# incubadora-v1.net
KiCad netlist of a schematic drawn in EAGLE
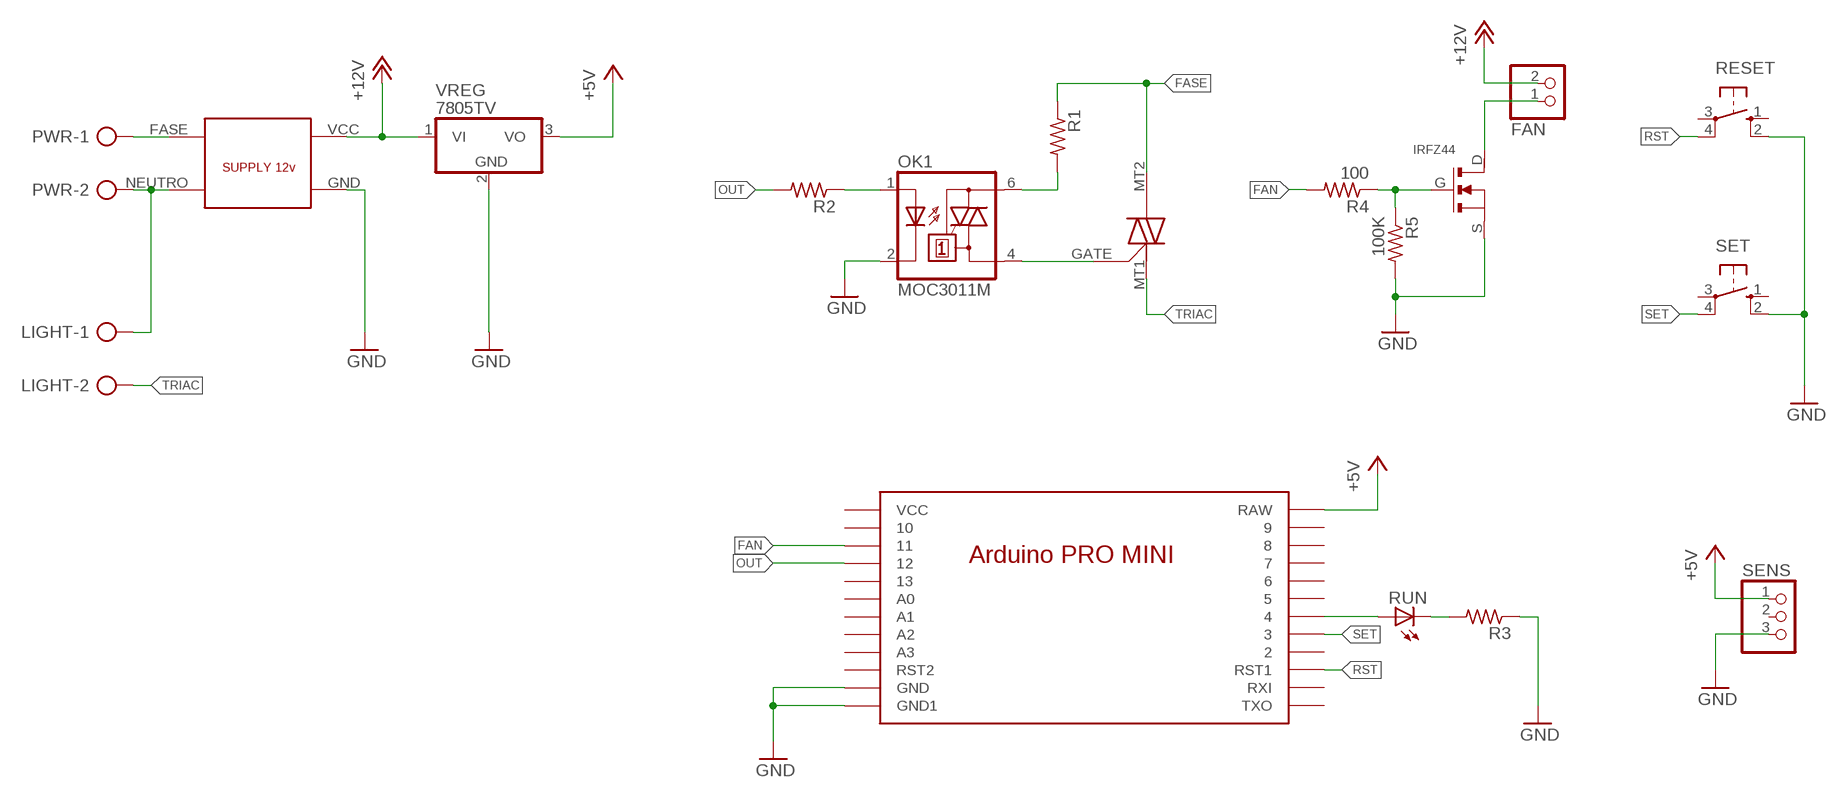
[diagram p0: schematic, sheet 1]

(export (version "E")
  (design (tool "Eeschema 10.0.6"))
  (components
    (comp (ref "FAN")
      (value "PINHD-1X2/90")
      (footprint "eagle-import:1X02_90")
      (libsource (lib "eagle-import") (part "PINHD-1X2/90"))
    )
    (comp (ref "IRFZ44")
      (value "IRFZ44")
      (footprint "eagle-import:IRFZ44")
      (libsource (lib "eagle-import") (part "IRFZ44"))
    )
    (comp (ref "LIGHT")
      (value "AK300/2")
      (footprint "eagle-import:AK300_2")
      (libsource (lib "eagle-import") (part "AK300/2"))
    )
    (comp (ref "OK1")
      (value "MOC3011M")
      (footprint "eagle-import:DIL06")
      (fields (field (name "MF") "FAIRCHILD SEMICONDUCTOR") (field (name "MPN") "MOC3011-M"))
      (libsource (lib "eagle-import") (part "MOC30M11"))
    )
    (comp (ref "PWR")
      (value "AK300/2")
      (footprint "eagle-import:AK300_2")
      (libsource (lib "eagle-import") (part "AK300/2"))
    )
    (comp (ref "R1")
      (value "R-US_0204/7")
      (footprint "eagle-import:0204_7")
      (libsource (lib "eagle-import") (part "R-US_0204/7"))
    )
    (comp (ref "R2")
      (value "R-US_0204/7")
      (footprint "eagle-import:0204_7")
      (libsource (lib "eagle-import") (part "R-US_0204/7"))
    )
    (comp (ref "R3")
      (value "R-US_0204/7")
      (footprint "eagle-import:0204_7")
      (libsource (lib "eagle-import") (part "R-US_0204/7"))
    )
    (comp (ref "R4")
      (value "100")
      (footprint "eagle-import:0204_7")
      (libsource (lib "eagle-import") (part "R-US_0204/7"))
    )
    (comp (ref "R5")
      (value "100K")
      (footprint "eagle-import:0204_7")
      (libsource (lib "eagle-import") (part "R-US_0204/7"))
    )
    (comp (ref "RESET")
      (value "10-XX")
      (footprint "eagle-import:B3F-10XX")
      (fields (field (name "MPN") "B3F-1000"))
      (libsource (lib "eagle-import") (part "10-XX"))
    )
    (comp (ref "RUN")
      (value "LED5MM")
      (footprint "eagle-import:LED5MM")
      (libsource (lib "eagle-import") (part "LED5MM"))
    )
    (comp (ref "SENS")
      (value "PINHD-1X3/90")
      (footprint "eagle-import:1X03_90")
      (libsource (lib "eagle-import") (part "PINHD-1X3/90"))
    )
    (comp (ref "SET")
      (value "10-XX")
      (footprint "eagle-import:B3F-10XX")
      (fields (field (name "MPN") "B3F-1000"))
      (libsource (lib "eagle-import") (part "10-XX"))
    )
    (comp (ref "TRIAC")
      (value "MAC12")
      (footprint "eagle-import:MAC12")
      (libsource (lib "eagle-import") (part "MAC12"))
    )
    (comp (ref "U$1")
      (value "NANO")
      (footprint "eagle-import:NANO")
      (libsource (lib "eagle-import") (part "NANO"))
    )
    (comp (ref "U$3")
      (value "SUPPLY12V")
      (footprint "eagle-import:SUPPLY12V")
      (libsource (lib "eagle-import") (part "SUPPLY12V"))
    )
    (comp (ref "VREG")
      (value "7805TV")
      (footprint "eagle-import:TO220V")
      (libsource (lib "eagle-import") (part "78TV05"))
    )
  )
  (nets
    (net (code "1") (name "+5V") (class "Default")
      (node (ref "SENS") (pin "1") (pinfunction "1_1") (pintype "passive"))
      (node (ref "U$1") (pin "RAW") (pinfunction "RAW_RAW") (pintype "bidirectional"))
      (node (ref "VREG") (pin "3") (pinfunction "VO_3") (pintype "passive"))
    )
    (net (code "2") (name "+12V") (class "Default")
      (node (ref "FAN") (pin "2") (pinfunction "2_2") (pintype "passive"))
      (node (ref "U$3") (pin "VCC") (pinfunction "VCC_VCC") (pintype "bidirectional"))
      (node (ref "VREG") (pin "1") (pinfunction "VI_1") (pintype "input"))
    )
    (net (code "3") (name "FAN") (class "Default")
      (node (ref "R4") (pin "2") (pinfunction "2_2") (pintype "passive"))
      (node (ref "U$1") (pin "11") (pinfunction "11_11") (pintype "bidirectional"))
    )
    (net (code "4") (name "FASE") (class "Default")
      (node (ref "PWR") (pin "1") (pinfunction "KL_1") (pintype "passive"))
      (node (ref "R1") (pin "1") (pinfunction "1_1") (pintype "passive"))
      (node (ref "TRIAC") (pin "MT2") (pinfunction "MT2_MT2") (pintype "bidirectional"))
      (node (ref "U$3") (pin "FASE") (pinfunction "FASE_FASE") (pintype "bidirectional"))
    )
    (net (code "5") (name "GND") (class "Default")
      (node (ref "IRFZ44") (pin "S") (pinfunction "S_S") (pintype "bidirectional"))
      (node (ref "OK1") (pin "2") (pinfunction "C_2") (pintype "passive"))
      (node (ref "R3") (pin "1") (pinfunction "1_1") (pintype "passive"))
      (node (ref "R5") (pin "2") (pinfunction "2_2") (pintype "passive"))
      (node (ref "RESET") (pin "2") (pinfunction "S1_2") (pintype "passive"))
      (node (ref "SENS") (pin "3") (pinfunction "3_3") (pintype "passive"))
      (node (ref "SET") (pin "2") (pinfunction "S1_2") (pintype "passive"))
      (node (ref "U$1") (pin "GND1") (pinfunction "GND_GND1") (pintype "bidirectional"))
      (node (ref "U$1") (pin "GND2") (pinfunction "GND1_GND2") (pintype "power_in"))
      (node (ref "U$3") (pin "GND") (pinfunction "GND_GND") (pintype "bidirectional"))
      (node (ref "VREG") (pin "2") (pinfunction "GND_2") (pintype "passive"))
    )
    (net (code "6") (name "Net-(FAN-Pad1)") (class "Default")
      (node (ref "FAN") (pin "1") (pinfunction "1_1") (pintype "passive"))
      (node (ref "IRFZ44") (pin "D") (pinfunction "D_D") (pintype "bidirectional"))
    )
    (net (code "7") (name "Net-(IRFZ44-PadG)") (class "Default")
      (node (ref "IRFZ44") (pin "G") (pinfunction "G_G") (pintype "bidirectional"))
      (node (ref "R4") (pin "1") (pinfunction "1_1") (pintype "passive"))
      (node (ref "R5") (pin "1") (pinfunction "1_1") (pintype "passive"))
    )
    (net (code "8") (name "Net-(LIGHTA-KL)") (class "Default")
      (node (ref "LIGHT") (pin "1") (pinfunction "KL_1") (pintype "passive"))
      (node (ref "PWR") (pin "2") (pinfunction "KL_2") (pintype "passive"))
      (node (ref "U$3") (pin "NEUTRO") (pinfunction "NEUTRO_NEUTRO") (pintype "bidirectional"))
    )
    (net (code "9") (name "Net-(OK1-A)") (class "Default")
      (node (ref "OK1") (pin "1") (pinfunction "A_1") (pintype "passive"))
      (node (ref "R2") (pin "1") (pinfunction "1_1") (pintype "passive"))
    )
    (net (code "10") (name "Net-(OK1-A1)") (class "Default")
      (node (ref "OK1") (pin "4") (pinfunction "A1_4") (pintype "passive"))
      (node (ref "TRIAC") (pin "GATE") (pinfunction "GATE_GATE") (pintype "bidirectional"))
    )
    (net (code "11") (name "Net-(OK1-A2)") (class "Default")
      (node (ref "OK1") (pin "6") (pinfunction "A2_6") (pintype "passive"))
      (node (ref "R1") (pin "2") (pinfunction "2_2") (pintype "passive"))
    )
    (net (code "12") (name "Net-(RUN-C)") (class "Default")
      (node (ref "R3") (pin "2") (pinfunction "2_2") (pintype "passive"))
      (node (ref "RUN") (pin "K") (pinfunction "C_K") (pintype "passive"))
    )
    (net (code "13") (name "Net-(RUN-PadA)") (class "Default")
      (node (ref "RUN") (pin "A") (pinfunction "A_A") (pintype "passive"))
      (node (ref "U$1") (pin "4") (pinfunction "4_4") (pintype "bidirectional"))
    )
    (net (code "14") (name "OUT") (class "Default")
      (node (ref "R2") (pin "2") (pinfunction "2_2") (pintype "passive"))
      (node (ref "U$1") (pin "12") (pinfunction "12_12") (pintype "bidirectional"))
    )
    (net (code "15") (name "RST") (class "Default")
      (node (ref "RESET") (pin "4") (pinfunction "P1_4") (pintype "passive"))
      (node (ref "U$1") (pin "RST1") (pinfunction "RST1_RST1") (pintype "bidirectional"))
    )
    (net (code "16") (name "SET") (class "Default")
      (node (ref "SET") (pin "4") (pinfunction "P1_4") (pintype "passive"))
      (node (ref "U$1") (pin "3") (pinfunction "3_3") (pintype "bidirectional"))
    )
    (net (code "17") (name "TRIAC") (class "Default")
      (node (ref "LIGHT") (pin "2") (pinfunction "KL_2") (pintype "passive"))
      (node (ref "TRIAC") (pin "MT1") (pinfunction "MT1_MT1") (pintype "bidirectional"))
    )
    (net (code "18") (name "unconnected-(RESET-P-Pad3)") (class "Default")
      (node (ref "RESET") (pin "3") (pinfunction "P_3") (pintype "passive"))
    )
    (net (code "19") (name "unconnected-(RESET-S-Pad1)") (class "Default")
      (node (ref "RESET") (pin "1") (pinfunction "S_1") (pintype "passive"))
    )
    (net (code "20") (name "unconnected-(SENS-Pad2)") (class "Default")
      (node (ref "SENS") (pin "2") (pinfunction "2_2") (pintype "passive"))
    )
    (net (code "21") (name "unconnected-(SET-P-Pad3)") (class "Default")
      (node (ref "SET") (pin "3") (pinfunction "P_3") (pintype "passive"))
    )
    (net (code "22") (name "unconnected-(SET-S-Pad1)") (class "Default")
      (node (ref "SET") (pin "1") (pinfunction "S_1") (pintype "passive"))
    )
    (net (code "23") (name "unconnected-(U$1-Pad2)") (class "Default")
      (node (ref "U$1") (pin "2") (pinfunction "2_2") (pintype "bidirectional"))
    )
    (net (code "24") (name "unconnected-(U$1-Pad5)") (class "Default")
      (node (ref "U$1") (pin "5") (pinfunction "5_5") (pintype "bidirectional"))
    )
    (net (code "25") (name "unconnected-(U$1-Pad6)") (class "Default")
      (node (ref "U$1") (pin "6") (pinfunction "6_6") (pintype "bidirectional"))
    )
    (net (code "26") (name "unconnected-(U$1-Pad7)") (class "Default")
      (node (ref "U$1") (pin "7") (pinfunction "7_7") (pintype "bidirectional"))
    )
    (net (code "27") (name "unconnected-(U$1-Pad8)") (class "Default")
      (node (ref "U$1") (pin "8") (pinfunction "8_8") (pintype "bidirectional"))
    )
    (net (code "28") (name "unconnected-(U$1-Pad9)") (class "Default")
      (node (ref "U$1") (pin "9") (pinfunction "9_9") (pintype "bidirectional"))
    )
    (net (code "29") (name "unconnected-(U$1-Pad10)") (class "Default")
      (node (ref "U$1") (pin "10") (pinfunction "10_10") (pintype "bidirectional"))
    )
    (net (code "30") (name "unconnected-(U$1-Pad13)") (class "Default")
      (node (ref "U$1") (pin "13") (pinfunction "13_13") (pintype "bidirectional"))
    )
    (net (code "31") (name "unconnected-(U$1-PadA0)") (class "Default")
      (node (ref "U$1") (pin "A0") (pinfunction "A0_A0") (pintype "bidirectional"))
    )
    (net (code "32") (name "unconnected-(U$1-PadA1)") (class "Default")
      (node (ref "U$1") (pin "A1") (pinfunction "A1_A1") (pintype "bidirectional"))
    )
    (net (code "33") (name "unconnected-(U$1-PadA2)") (class "Default")
      (node (ref "U$1") (pin "A2") (pinfunction "A2_A2") (pintype "bidirectional"))
    )
    (net (code "34") (name "unconnected-(U$1-PadA3)") (class "Default")
      (node (ref "U$1") (pin "A3") (pinfunction "A3_A3") (pintype "bidirectional"))
    )
    (net (code "35") (name "unconnected-(U$1-PadRST2)") (class "Default")
      (node (ref "U$1") (pin "RST2") (pinfunction "RST2_RST2") (pintype "bidirectional"))
    )
    (net (code "36") (name "unconnected-(U$1-PadRXI)") (class "Default")
      (node (ref "U$1") (pin "RXI") (pinfunction "RXI_RXI") (pintype "bidirectional"))
    )
    (net (code "37") (name "unconnected-(U$1-PadTXO)") (class "Default")
      (node (ref "U$1") (pin "TXO") (pinfunction "TXO_TXO") (pintype "bidirectional"))
    )
    (net (code "38") (name "unconnected-(U$1-PadVCC)") (class "Default")
      (node (ref "U$1") (pin "VCC") (pinfunction "VCC_VCC") (pintype "bidirectional"))
    )
  )
)
